# harvesting2.net
KiCad netlist of a schematic drawn in Altium Designer
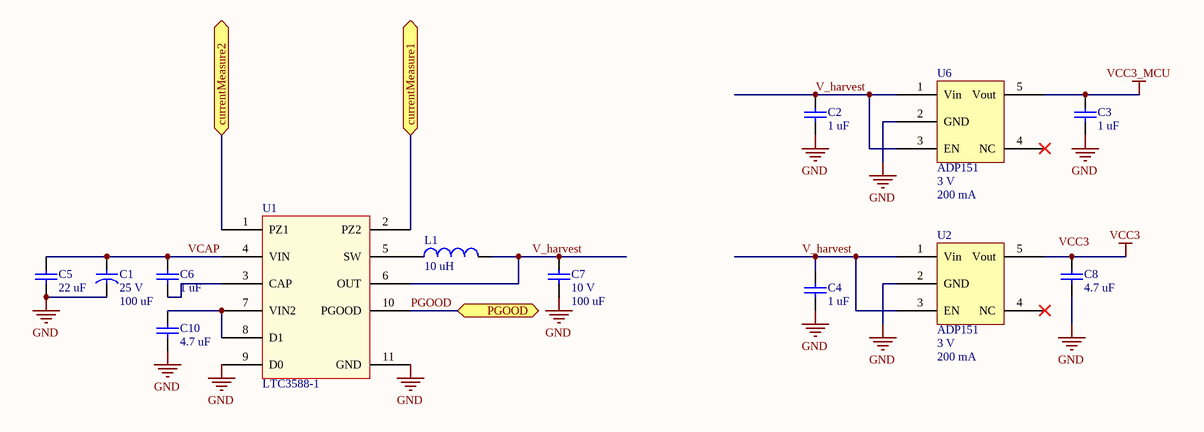
[diagram p0: harvesting2.SchDoc]

(export (version "E")
  (design (tool "Eeschema 10.0.6"))
  (components
    (comp (ref "C1")
      (value "100 uF")
      (footprint "2917")
      (description "Tantalum capacitor, 100u, 2917 package")
      (fields
        (field (name "TOLERANCE") "10%")
        (field (name "VOLTAGE RATED") "25 V")
        (field (name "Comment") "Ceramic capacitor")
      )
      (libsource (lib "rlc") (part "C_100u_25V_2917_tantalum"))
    )
    (comp (ref "C2")
      (value "1 uF")
      (footprint "0402")
      (description "Ceramic capacitor, 1 uF, 16V, 0402 package")
      (fields (field (name "TOLERANCE") "10%") (field (name "Comment") "Ceramic capacitor"))
      (libsource (lib "rlc") (part "C_1u_16V_0402_ceramic"))
    )
    (comp (ref "C3")
      (value "1 uF")
      (footprint "0402")
      (description "Ceramic capacitor, 1 uF, 16V, 0402 package")
      (fields (field (name "TOLERANCE") "10%") (field (name "Comment") "Ceramic capacitor"))
      (libsource (lib "rlc") (part "C_1u_16V_0402_ceramic"))
    )
    (comp (ref "C4")
      (value "1 uF")
      (footprint "0402")
      (description "Ceramic capacitor, 1 uF, 16V, 0402 package")
      (fields (field (name "TOLERANCE") "10%") (field (name "Comment") "Ceramic capacitor"))
      (libsource (lib "rlc") (part "C_1u_16V_0402_ceramic"))
    )
    (comp (ref "C5")
      (value "22 uF")
      (footprint "1206")
      (description "Ceramic capacitor, 22 uF, 35 V, 1206 package")
      (fields (field (name "TOLERANCE") "20%") (field (name "Comment") "Ceramic capacitor"))
      (libsource (lib "rlc") (part "C_22u_35V_1206_ceramic"))
    )
    (comp (ref "C6")
      (value "1 uF")
      (footprint "0402")
      (description "Ceramic capacitor, 1 uF, 16V, 0402 package")
      (fields (field (name "TOLERANCE") "10%") (field (name "Comment") "Ceramic capacitor"))
      (libsource (lib "rlc") (part "C_1u_16V_0402_ceramic"))
    )
    (comp (ref "C7")
      (value "100 uF")
      (footprint "1210")
      (description "Ceramic capacitor, 100u, 1210 package")
      (fields
        (field (name "TOLERANCE") "20%")
        (field (name "VOLTAGE RATED") "10 V")
        (field (name "Comment") "Ceramic capacitor")
      )
      (libsource (lib "rlc") (part "C_100u_10V_1210_ceramic"))
    )
    (comp (ref "C8")
      (value "4.7 uF")
      (footprint "0603")
      (description "Ceramic capacitor, 4.7u, 10V, 0603 package")
      (fields (field (name "TOLERANCE") "20%") (field (name "Comment") "Ceramic capacitor"))
      (libsource (lib "rlc") (part "C_4.7u_10V_0603_ceramic"))
    )
    (comp (ref "C10")
      (value "4.7 uF")
      (footprint "0603")
      (description "Ceramic capacitor, 4.7u, 10V, 0603 package")
      (fields (field (name "TOLERANCE") "20%") (field (name "Comment") "Ceramic capacitor"))
      (libsource (lib "rlc") (part "C_4.7u_10V_0603_ceramic"))
    )
    (comp (ref "L1")
      (value "10 uH")
      (footprint "CDRH2D18")
      (description "Chip inductor, 10 uH,  1A, 180 mOhm")
      (fields (field (name "TOLERANCE") "30%") (field (name "Comment") "Chip inductor"))
      (libsource (lib "rlc") (part "L_10uH_1A_180m"))
    )
    (comp (ref "U1")
      (value "LTC3588-1")
      (footprint "TSSOP50P490X110_HS-11N")
      (description "Piezoelectric Energy   Harvesting Power Supply")
      (libsource (lib "coilcube_frontend") (part "LTC3588-1"))
    )
    (comp (ref "U2")
      (value "ADP151")
      (footprint "SOT23-5")
      (description "Ultralow Noise, 200 mA,  CMOS Linear Regulator")
      (fields (field (name "VOLTAGE") "3 V") (field (name "CURRENT") "200 mA"))
      (libsource (lib "voltage_regulators") (part "ADP151"))
    )
    (comp (ref "U6")
      (value "ADP151")
      (footprint "SOT23-5")
      (description "Ultralow Noise, 200 mA,  CMOS Linear Regulator")
      (fields (field (name "VOLTAGE") "3 V") (field (name "CURRENT") "200 mA"))
      (libsource (lib "voltage_regulators") (part "ADP151"))
    )
  )
  (nets
    (net (code "1") (name "/PGOOD") (class "Default")
      (node (ref "U1") (pin "10") (pinfunction "PGOOD_10") (pintype "passive"))
    )
    (net (code "2") (name "/VCAP") (class "Default")
      (node (ref "C1") (pin "1") (pintype "passive"))
      (node (ref "C5") (pin "1") (pintype "passive"))
      (node (ref "C6") (pin "1") (pintype "passive"))
      (node (ref "U1") (pin "4") (pinfunction "VIN_4") (pintype "passive"))
    )
    (net (code "3") (name "/V_harvest") (class "Default")
      (node (ref "C2") (pin "1") (pintype "passive"))
      (node (ref "C4") (pin "1") (pintype "passive"))
      (node (ref "C7") (pin "1") (pintype "passive"))
      (node (ref "L1") (pin "1") (pintype "passive"))
      (node (ref "U1") (pin "6") (pinfunction "OUT_6") (pintype "passive"))
      (node (ref "U2") (pin "1") (pinfunction "Vin_1") (pintype "passive"))
      (node (ref "U2") (pin "3") (pinfunction "EN_3") (pintype "passive"))
      (node (ref "U6") (pin "1") (pinfunction "Vin_1") (pintype "passive"))
      (node (ref "U6") (pin "3") (pinfunction "EN_3") (pintype "passive"))
    )
    (net (code "4") (name "/currentMeasure1") (class "Default")
      (node (ref "U1") (pin "2") (pinfunction "PZ2_2") (pintype "passive"))
    )
    (net (code "5") (name "/currentMeasure2") (class "Default")
      (node (ref "U1") (pin "1") (pinfunction "PZ1_1") (pintype "passive"))
    )
    (net (code "6") (name "GND") (class "Default")
      (node (ref "C1") (pin "2") (pintype "passive"))
      (node (ref "C10") (pin "2") (pintype "passive"))
      (node (ref "C2") (pin "2") (pintype "passive"))
      (node (ref "C3") (pin "2") (pintype "passive"))
      (node (ref "C4") (pin "2") (pintype "passive"))
      (node (ref "C5") (pin "2") (pintype "passive"))
      (node (ref "C7") (pin "2") (pintype "passive"))
      (node (ref "C8") (pin "2") (pintype "passive"))
      (node (ref "U1") (pin "11") (pinfunction "GND_11") (pintype "passive"))
      (node (ref "U1") (pin "9") (pinfunction "D0_9") (pintype "passive"))
      (node (ref "U2") (pin "2") (pinfunction "GND_2") (pintype "passive"))
      (node (ref "U6") (pin "2") (pinfunction "GND_2") (pintype "passive"))
    )
    (net (code "7") (name "Net-(U1-CAP)") (class "Default")
      (node (ref "C6") (pin "2") (pintype "passive"))
      (node (ref "U1") (pin "3") (pinfunction "CAP_3") (pintype "passive"))
    )
    (net (code "8") (name "Net-(U1-D1)") (class "Default")
      (node (ref "C10") (pin "1") (pintype "passive"))
      (node (ref "U1") (pin "7") (pinfunction "VIN2_7") (pintype "passive"))
      (node (ref "U1") (pin "8") (pinfunction "D1_8") (pintype "passive"))
    )
    (net (code "9") (name "Net-(U1-SW)") (class "Default")
      (node (ref "L1") (pin "2") (pintype "passive"))
      (node (ref "U1") (pin "5") (pinfunction "SW_5") (pintype "passive"))
    )
    (net (code "10") (name "VCC3") (class "Default")
      (node (ref "C8") (pin "1") (pintype "passive"))
      (node (ref "U2") (pin "5") (pinfunction "Vout_5") (pintype "passive"))
    )
    (net (code "11") (name "VCC3_MCU") (class "Default")
      (node (ref "C3") (pin "1") (pintype "passive"))
      (node (ref "U6") (pin "5") (pinfunction "Vout_5") (pintype "passive"))
    )
    (net (code "12") (name "unconnected-(U2-NC-Pad4)") (class "Default")
      (node (ref "U2") (pin "4") (pinfunction "NC_4") (pintype "passive+no_connect"))
    )
    (net (code "13") (name "unconnected-(U6-NC-Pad4)") (class "Default")
      (node (ref "U6") (pin "4") (pinfunction "NC_4") (pintype "passive+no_connect"))
    )
  )
)
